# Hall_Effect_Power.net
KiCad netlist of a schematic drawn in EAGLE
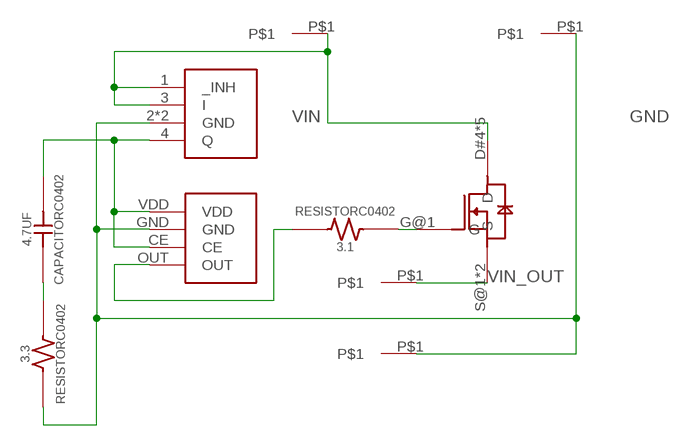
[diagram p0: schematic, sheet 1]

(export (version "E")
  (design (tool "Eeschema 10.0.6"))
  (components
    (comp (ref "3.1")
      (value "RESISTORC0402")
      (footprint "eagle-import:C0402")
      (fields (field (name "MANF") "Samsung Electro-Mechanics America, Inc."))
      (libsource (lib "eagle-import") (part "RESISTORC0402"))
    )
    (comp (ref "3.3")
      (value "RESISTORC0402")
      (footprint "eagle-import:C0402")
      (fields (field (name "MANF") "Yageo"))
      (libsource (lib "eagle-import") (part "RESISTORC0402"))
    )
    (comp (ref "4.7UF")
      (value "CAPACITORC0402")
      (footprint "eagle-import:C0402")
      (fields (field (name "MANF") "Samsung Electro-Mechanics America, Inc."))
      (libsource (lib "eagle-import") (part "CAPACITORC0402"))
    )
    (comp (ref "U$1")
      (value "HALL-MOSFET-NEW")
      (footprint "eagle-import:HALL-MOSFET-NEW")
      (fields (field (name "MANF") "Vishay Siliconix"))
      (libsource (lib "eagle-import") (part "HALL-MOSFET-NEW"))
    )
    (comp (ref "U$2")
      (value "HALL-HALL-NEW")
      (footprint "eagle-import:HALL-HALL-NEW")
      (fields (field (name "MANF") "SII Semiconductor Corporation"))
      (libsource (lib "eagle-import") (part "HALL-HALL-NEW"))
    )
    (comp (ref "U$3")
      (value "HALL-REG-NEW")
      (footprint "eagle-import:HALL-REG-NEW")
      (fields (field (name "MANF") "Infineon Technologies"))
      (libsource (lib "eagle-import") (part "HALL-REG-NEW"))
    )
    (comp (ref "U$4")
      (value "SINGLE-WIRE")
      (footprint "eagle-import:SINGLE-WIRE")
      (libsource (lib "eagle-import") (part "SINGLE-WIRE"))
    )
    (comp (ref "U$5")
      (value "SINGLE-WIRE")
      (footprint "eagle-import:SINGLE-WIRE")
      (libsource (lib "eagle-import") (part "SINGLE-WIRE"))
    )
    (comp (ref "U$6")
      (value "SINGLE-WIRE")
      (footprint "eagle-import:SINGLE-WIRE")
      (libsource (lib "eagle-import") (part "SINGLE-WIRE"))
    )
    (comp (ref "U$7")
      (value "SINGLE-WIRE")
      (footprint "eagle-import:SINGLE-WIRE")
      (libsource (lib "eagle-import") (part "SINGLE-WIRE"))
    )
  )
  (nets
    (net (code "1") (name "/GND") (class "Default")
      (node (ref "3.3") (pin "1") (pinfunction "P$1_1") (pintype "bidirectional"))
      (node (ref "U$2") (pin "GND") (pinfunction "GND_GND") (pintype "bidirectional"))
      (node (ref "U$3") (pin "2") (pinfunction "GND_2") (pintype "bidirectional"))
      (node (ref "U$3") (pin "5") (pinfunction "GND_5") (pintype "bidirectional"))
      (node (ref "U$4") (pin "P$1") (pinfunction "P$1_P$1") (pintype "bidirectional"))
      (node (ref "U$7") (pin "P$1") (pinfunction "P$1_P$1") (pintype "bidirectional"))
    )
    (net (code "2") (name "/VIN") (class "Default")
      (node (ref "U$1") (pin "D#4") (pinfunction "D_D#4") (pintype "bidirectional"))
      (node (ref "U$1") (pin "D@1") (pinfunction "D_D@1") (pintype "bidirectional"))
      (node (ref "U$1") (pin "D@2") (pinfunction "D_D@2") (pintype "bidirectional"))
      (node (ref "U$1") (pin "D@3") (pinfunction "D_D@3") (pintype "bidirectional"))
      (node (ref "U$1") (pin "D@5") (pinfunction "D_D@5") (pintype "bidirectional"))
      (node (ref "U$3") (pin "1") (pinfunction "_INH_1") (pintype "bidirectional"))
      (node (ref "U$3") (pin "3") (pinfunction "I_3") (pintype "bidirectional"))
      (node (ref "U$6") (pin "P$1") (pinfunction "P$1_P$1") (pintype "bidirectional"))
    )
    (net (code "3") (name "/VIN_OUT") (class "Default")
      (node (ref "U$1") (pin "S@1") (pinfunction "S_S@1") (pintype "bidirectional"))
      (node (ref "U$1") (pin "S@2") (pinfunction "S_S@2") (pintype "bidirectional"))
      (node (ref "U$5") (pin "P$1") (pinfunction "P$1_P$1") (pintype "bidirectional"))
    )
    (net (code "4") (name "Net-(3.1-P$1)") (class "Default")
      (node (ref "3.1") (pin "1") (pinfunction "P$1_1") (pintype "bidirectional"))
      (node (ref "U$1") (pin "G@1") (pinfunction "G_G@1") (pintype "bidirectional"))
    )
    (net (code "5") (name "Net-(3.1-P$2)") (class "Default")
      (node (ref "3.1") (pin "2") (pinfunction "P$2_2") (pintype "bidirectional"))
      (node (ref "U$2") (pin "OUT") (pinfunction "OUT_OUT") (pintype "bidirectional"))
    )
    (net (code "6") (name "Net-(3.3-P$2)") (class "Default")
      (node (ref "3.3") (pin "2") (pinfunction "P$2_2") (pintype "bidirectional"))
      (node (ref "4.7UF") (pin "1") (pinfunction "A_1") (pintype "bidirectional"))
    )
    (net (code "7") (name "Net-(4.7UF-B)") (class "Default")
      (node (ref "4.7UF") (pin "2") (pinfunction "B_2") (pintype "bidirectional"))
      (node (ref "U$2") (pin "CE") (pinfunction "CE_CE") (pintype "bidirectional"))
      (node (ref "U$2") (pin "VDD") (pinfunction "VDD_VDD") (pintype "bidirectional"))
      (node (ref "U$3") (pin "4") (pinfunction "Q_4") (pintype "bidirectional"))
    )
  )
)
